# board_revB.net
KiCad netlist of a schematic drawn in EAGLE
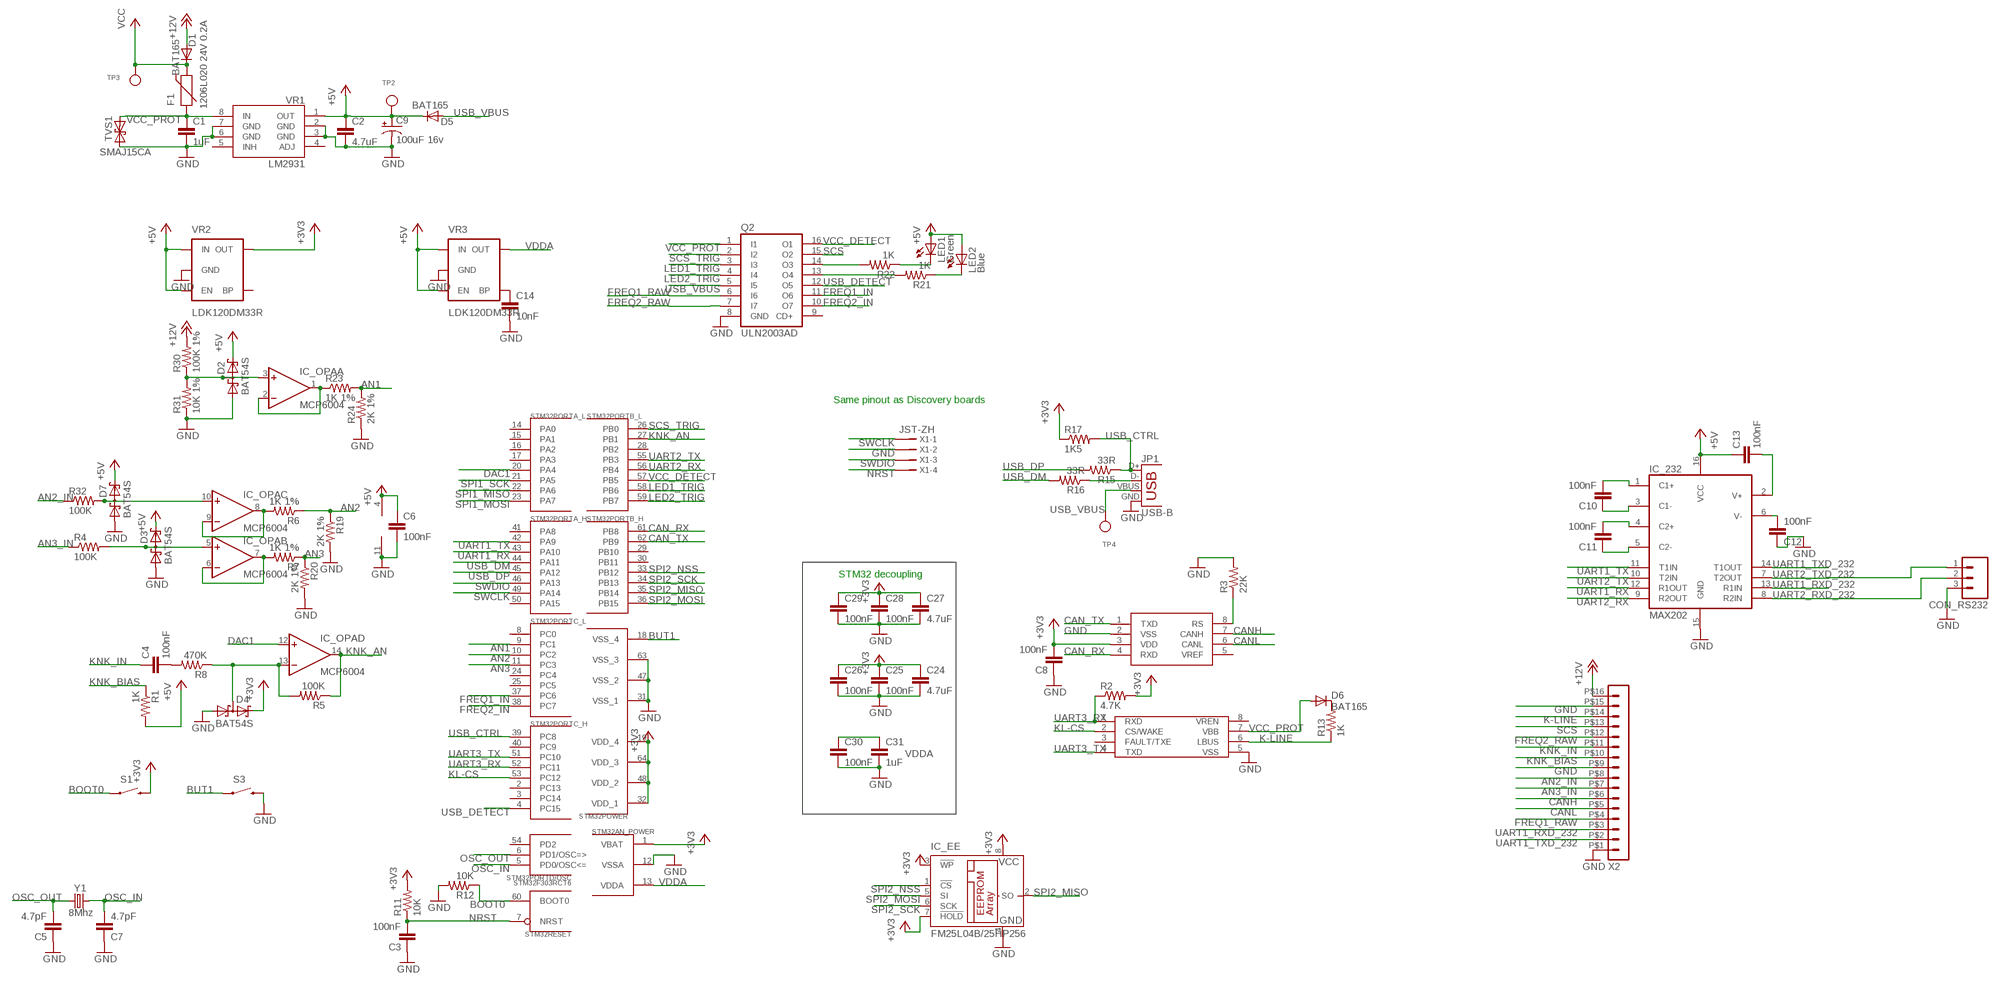
[diagram p0: schematic, sheet 1]

(export (version "E")
  (design (tool "Eeschema 10.0.6"))
  (components
    (comp (ref "C1")
      (value "1uF")
      (footprint "eagle-import:0603-CAP")
      (libsource (lib "eagle-import") (part "SparkFun-Passives_CAP0603-CAP"))
    )
    (comp (ref "C2")
      (value "4.7uF")
      (footprint "eagle-import:0603-CAP")
      (libsource (lib "eagle-import") (part "SparkFun-Passives_CAP0603-CAP"))
    )
    (comp (ref "C3")
      (value "100nF")
      (footprint "eagle-import:0603-CAP")
      (libsource (lib "eagle-import") (part "CAP0603-CAP"))
    )
    (comp (ref "C4")
      (value "100nF")
      (footprint "eagle-import:0603-CAP")
      (libsource (lib "eagle-import") (part "CAP0603-CAP"))
    )
    (comp (ref "C5")
      (value "4.7pF")
      (footprint "eagle-import:0603-CAP")
      (libsource (lib "eagle-import") (part "CAP0603-CAP"))
    )
    (comp (ref "C6")
      (value "100nF")
      (footprint "eagle-import:0603-CAP")
      (libsource (lib "eagle-import") (part "CAP0603-CAP"))
    )
    (comp (ref "C7")
      (value "4.7pF")
      (footprint "eagle-import:0603-CAP")
      (libsource (lib "eagle-import") (part "CAP0603-CAP"))
    )
    (comp (ref "C8")
      (value "100nF")
      (footprint "eagle-import:0603-CAP")
      (libsource (lib "eagle-import") (part "CAP0603-CAP"))
    )
    (comp (ref "C9")
      (value "100uF 16v")
      (footprint "eagle-import:CPOL-RADIAL-10UF-25V")
      (libsource (lib "eagle-import") (part "CAP_POLPTH2"))
    )
    (comp (ref "C10")
      (value "100nF")
      (footprint "eagle-import:0603-CAP")
      (libsource (lib "eagle-import") (part "CAP0603-CAP"))
    )
    (comp (ref "C11")
      (value "100nF")
      (footprint "eagle-import:0603-CAP")
      (libsource (lib "eagle-import") (part "CAP0603-CAP"))
    )
    (comp (ref "C12")
      (value "100nF")
      (footprint "eagle-import:0603-CAP")
      (libsource (lib "eagle-import") (part "CAP0603-CAP"))
    )
    (comp (ref "C13")
      (value "100nF")
      (footprint "eagle-import:0603-CAP")
      (libsource (lib "eagle-import") (part "CAP0603-CAP"))
    )
    (comp (ref "C14")
      (value "10nF")
      (footprint "eagle-import:0603-CAP")
      (libsource (lib "eagle-import") (part "CAP0603-CAP"))
    )
    (comp (ref "C24")
      (value "4.7uF")
      (footprint "eagle-import:0603-CAP")
      (libsource (lib "eagle-import") (part "SparkFun-Passives_CAP0603-CAP"))
    )
    (comp (ref "C25")
      (value "100nF")
      (footprint "eagle-import:0603-CAP")
      (libsource (lib "eagle-import") (part "CAP0603-CAP"))
    )
    (comp (ref "C26")
      (value "100nF")
      (footprint "eagle-import:0603-CAP")
      (libsource (lib "eagle-import") (part "CAP0603-CAP"))
    )
    (comp (ref "C27")
      (value "4.7uF")
      (footprint "eagle-import:0603-CAP")
      (libsource (lib "eagle-import") (part "SparkFun-Passives_CAP0603-CAP"))
    )
    (comp (ref "C28")
      (value "100nF")
      (footprint "eagle-import:0603-CAP")
      (libsource (lib "eagle-import") (part "CAP0603-CAP"))
    )
    (comp (ref "C29")
      (value "100nF")
      (footprint "eagle-import:0603-CAP")
      (libsource (lib "eagle-import") (part "CAP0603-CAP"))
    )
    (comp (ref "C30")
      (value "100nF")
      (footprint "eagle-import:0603-CAP")
      (libsource (lib "eagle-import") (part "CAP0603-CAP"))
    )
    (comp (ref "C31")
      (value "1uF")
      (footprint "eagle-import:0603-CAP")
      (libsource (lib "eagle-import") (part "CAP0603-CAP"))
    )
    (comp (ref "CON_RS232")
      (value "M03LOCK")
      (footprint "eagle-import:1X03_LOCK")
      (libsource (lib "eagle-import") (part "M03LOCK"))
    )
    (comp (ref "D1")
      (value "BAT165")
      (footprint "eagle-import:SOD-323")
      (libsource (lib "eagle-import") (part "DIODESOD"))
    )
    (comp (ref "D2")
      (value "BAT54S")
      (footprint "eagle-import:SOT23")
      (libsource (lib "eagle-import") (part "BAT54S"))
    )
    (comp (ref "D3")
      (value "BAT54S")
      (footprint "eagle-import:SOT23")
      (libsource (lib "eagle-import") (part "BAT54S"))
    )
    (comp (ref "D4")
      (value "BAT54S")
      (footprint "eagle-import:SOT23")
      (libsource (lib "eagle-import") (part "BAT54S"))
    )
    (comp (ref "D5")
      (value "BAT165")
      (footprint "eagle-import:SOD-323")
      (libsource (lib "eagle-import") (part "DIODESOD"))
    )
    (comp (ref "D6")
      (value "BAT165")
      (footprint "eagle-import:SOD-323")
      (libsource (lib "eagle-import") (part "DIODESOD"))
    )
    (comp (ref "D7")
      (value "BAT54S")
      (footprint "eagle-import:SOT23")
      (libsource (lib "eagle-import") (part "BAT54S"))
    )
    (comp (ref "F1")
      (value "1206L020 24V 0.2A")
      (footprint "eagle-import:PTC-1206")
      (libsource (lib "eagle-import") (part "PTCSMD"))
    )
    (comp (ref "IC_232")
      (value "MAX202")
      (footprint "eagle-import:TSSOP16")
      (libsource (lib "eagle-import") (part "MAX232TSSOP"))
    )
    (comp (ref "IC_CAN")
      (value "MAX3051")
      (footprint "eagle-import:SO08")
      (libsource (lib "eagle-import") (part "MCP2551"))
    )
    (comp (ref "IC_EE")
      (value "FM25L04B/25HP256")
      (footprint "eagle-import:SO-08")
      (fields (field (name "MF") "MICROCHIP") (field (name "MPN") "25LC080/SN"))
      (libsource (lib "eagle-import") (part "25SNLC080"))
    )
    (comp (ref "IC_KLINE")
      (value "TJA1027")
      (footprint "eagle-import:SO08")
      (libsource (lib "eagle-import") (part "MCP2004"))
    )
    (comp (ref "IC_OPA")
      (value "MCP6004")
      (footprint "eagle-import:TSSOP14")
      (libsource (lib "eagle-import") (part "LMV324?MZ"))
    )
    (comp (ref "JP1")
      (value "USB-B")
      (footprint "eagle-import:USB-B-PTH")
      (libsource (lib "eagle-import") (part "USBPTH"))
    )
    (comp (ref "LED1")
      (value "Green")
      (footprint "eagle-import:LED3MM")
      (libsource (lib "eagle-import") (part "LED3MM"))
    )
    (comp (ref "LED2")
      (value "Blue")
      (footprint "eagle-import:LED3MM")
      (libsource (lib "eagle-import") (part "LED3MM"))
    )
    (comp (ref "Q2")
      (value "ULN2003AD")
      (footprint "eagle-import:SO16")
      (libsource (lib "eagle-import") (part "ULN2003AD"))
    )
    (comp (ref "R1")
      (value "1K")
      (footprint "eagle-import:0603-RES")
      (libsource (lib "eagle-import") (part "RESISTOR0603-RES"))
    )
    (comp (ref "R2")
      (value "4.7K")
      (footprint "eagle-import:0603-RES")
      (libsource (lib "eagle-import") (part "RESISTOR0603-RES"))
    )
    (comp (ref "R3")
      (value "22K")
      (footprint "eagle-import:0603-RES")
      (libsource (lib "eagle-import") (part "RESISTOR0603-RES"))
    )
    (comp (ref "R4")
      (value "100K")
      (footprint "eagle-import:0603-RES")
      (libsource (lib "eagle-import") (part "RESISTOR0603-RES"))
    )
    (comp (ref "R5")
      (value "100K")
      (footprint "eagle-import:0603-RES")
      (libsource (lib "eagle-import") (part "RESISTOR0603-RES"))
    )
    (comp (ref "R6")
      (value "1K 1%")
      (footprint "eagle-import:0603-RES")
      (libsource (lib "eagle-import") (part "RESISTOR0603-RES"))
    )
    (comp (ref "R7")
      (value "1K 1%")
      (footprint "eagle-import:0603-RES")
      (libsource (lib "eagle-import") (part "RESISTOR0603-RES"))
    )
    (comp (ref "R8")
      (value "470K")
      (footprint "eagle-import:0603-RES")
      (libsource (lib "eagle-import") (part "RESISTOR0603-RES"))
    )
    (comp (ref "R11")
      (value "10K")
      (footprint "eagle-import:0603-RES")
      (libsource (lib "eagle-import") (part "RESISTOR0603-RES"))
    )
    (comp (ref "R12")
      (value "10K")
      (footprint "eagle-import:0603-RES")
      (libsource (lib "eagle-import") (part "RESISTOR0603-RES"))
    )
    (comp (ref "R13")
      (value "1K")
      (footprint "eagle-import:0603-RES")
      (libsource (lib "eagle-import") (part "RESISTOR0603-RES"))
    )
    (comp (ref "R15")
      (value "33R")
      (footprint "eagle-import:0603-RES")
      (libsource (lib "eagle-import") (part "RESISTOR0603-RES"))
    )
    (comp (ref "R16")
      (value "33R")
      (footprint "eagle-import:0603-RES")
      (libsource (lib "eagle-import") (part "RESISTOR0603-RES"))
    )
    (comp (ref "R17")
      (value "1K5")
      (footprint "eagle-import:0603-RES")
      (libsource (lib "eagle-import") (part "RESISTOR0603-RES"))
    )
    (comp (ref "R19")
      (value "2K 1%")
      (footprint "eagle-import:0603-RES")
      (libsource (lib "eagle-import") (part "RESISTOR0603-RES"))
    )
    (comp (ref "R20")
      (value "2K 1%")
      (footprint "eagle-import:0603-RES")
      (libsource (lib "eagle-import") (part "RESISTOR0603-RES"))
    )
    (comp (ref "R21")
      (value "1K")
      (footprint "eagle-import:0603-RES")
      (libsource (lib "eagle-import") (part "RESISTOR0603-RES"))
    )
    (comp (ref "R22")
      (value "1K")
      (footprint "eagle-import:0603-RES")
      (libsource (lib "eagle-import") (part "RESISTOR0603-RES"))
    )
    (comp (ref "R23")
      (value "1K 1%")
      (footprint "eagle-import:0603-RES")
      (libsource (lib "eagle-import") (part "RESISTOR0603-RES"))
    )
    (comp (ref "R24")
      (value "2K 1%")
      (footprint "eagle-import:0603-RES")
      (libsource (lib "eagle-import") (part "RESISTOR0603-RES"))
    )
    (comp (ref "R30")
      (value "100K 1%")
      (footprint "eagle-import:0603-RES")
      (libsource (lib "eagle-import") (part "RESISTOR0603-RES"))
    )
    (comp (ref "R31")
      (value "10K 1%")
      (footprint "eagle-import:0603-RES")
      (libsource (lib "eagle-import") (part "RESISTOR0603-RES"))
    )
    (comp (ref "R32")
      (value "100K")
      (footprint "eagle-import:0603-RES")
      (libsource (lib "eagle-import") (part "RESISTOR0603-RES"))
    )
    (comp (ref "S1")
      (value "SWITCH-MOMENTARY-2SMD-4")
      (footprint "eagle-import:TACTILE_SWITCH_TALL")
      (libsource (lib "eagle-import") (part "SWITCH-MOMENTARY-2SMD-4"))
    )
    (comp (ref "S3")
      (value "SWITCH-MOMENTARY-2SIDE_EZ")
      (footprint "eagle-import:TACTILE-PTH-SIDEEZ")
      (libsource (lib "eagle-import") (part "SWITCH-MOMENTARY-2SIDE_EZ"))
    )
    (comp (ref "STM32")
      (value "STM32F303RCT6")
      (footprint "eagle-import:TQFP64")
      (libsource (lib "eagle-import") (part "STM32F10XRXT6"))
    )
    (comp (ref "TP2")
      (value "TESTPOINTROUND1MM")
      (footprint "eagle-import:TESTPOINT_ROUND_1MM")
      (libsource (lib "eagle-import") (part "TESTPOINTROUND1MM"))
    )
    (comp (ref "TP3")
      (value "TESTPOINTROUND1MM")
      (footprint "eagle-import:TESTPOINT_ROUND_1MM")
      (libsource (lib "eagle-import") (part "TESTPOINTROUND1MM"))
    )
    (comp (ref "TP4")
      (value "TESTPOINTROUND1MM")
      (footprint "eagle-import:TESTPOINT_ROUND_1MM")
      (libsource (lib "eagle-import") (part "TESTPOINTROUND1MM"))
    )
    (comp (ref "TVS1")
      (value "SMAJ15CA")
      (footprint "eagle-import:SMA-DIODE")
      (libsource (lib "eagle-import") (part "TVS"))
    )
    (comp (ref "VR1")
      (value "LM2931")
      (footprint "eagle-import:SO08")
      (libsource (lib "eagle-import") (part "LM2931"))
    )
    (comp (ref "VR2")
      (value "LDK120DM33R")
      (footprint "eagle-import:SOT23-5")
      (libsource (lib "eagle-import") (part "V_REG_LDOSMD"))
    )
    (comp (ref "VR3")
      (value "LDK120DM33R")
      (footprint "eagle-import:SOT23-5")
      (libsource (lib "eagle-import") (part "V_REG_LDOSMD"))
    )
    (comp (ref "X1")
      (value "JST-ZH")
      (footprint "eagle-import:S4B-ZR")
      (fields (field (name "MF") "FARNELL") (field (name "MPN") "S4B-ZR(LF)(SN)"))
      (libsource (lib "eagle-import") (part "?4B-ZRS"))
    )
    (comp (ref "X2")
      (value "HEADER_POS16_43045-1600")
      (footprint "eagle-import:43045-1600")
      (libsource (lib "eagle-import") (part "HEADER_POS16_?43045-1600"))
    )
    (comp (ref "Y1")
      (value "8Mhz")
      (footprint "eagle-import:HC49US")
      (libsource (lib "eagle-import") (part "CRYSTALHC49US"))
    )
  )
  (nets
    (net (code "1") (name "+3V3") (class "Default")
      (node (ref "C24") (pin "1") (pinfunction "1_1") (pintype "passive"))
      (node (ref "C25") (pin "1") (pinfunction "1_1") (pintype "passive"))
      (node (ref "C26") (pin "1") (pinfunction "1_1") (pintype "passive"))
      (node (ref "C27") (pin "1") (pinfunction "1_1") (pintype "passive"))
      (node (ref "C28") (pin "1") (pinfunction "1_1") (pintype "passive"))
      (node (ref "C29") (pin "1") (pinfunction "1_1") (pintype "passive"))
      (node (ref "C8") (pin "2") (pinfunction "2_2") (pintype "passive"))
      (node (ref "D4") (pin "2") (pinfunction "C2_2") (pintype "passive"))
      (node (ref "IC_CAN") (pin "3") (pinfunction "VDD_3") (pintype "bidirectional"))
      (node (ref "IC_EE") (pin "3") (pinfunction "~{WP}_3") (pintype "input"))
      (node (ref "IC_EE") (pin "7") (pinfunction "~{HOLD}_7") (pintype "input"))
      (node (ref "IC_EE") (pin "8") (pinfunction "VCC_8") (pintype "power_in"))
      (node (ref "R11") (pin "2") (pinfunction "2_2") (pintype "passive"))
      (node (ref "R17") (pin "1") (pinfunction "1_1") (pintype "passive"))
      (node (ref "R2") (pin "2") (pinfunction "2_2") (pintype "passive"))
      (node (ref "S1") (pin "B2") (pinfunction "2_B2") (pintype "passive"))
      (node (ref "STM32") (pin "1") (pinfunction "VBAT_1") (pintype "power_in"))
      (node (ref "STM32") (pin "19") (pinfunction "VDD_4_19") (pintype "power_in"))
      (node (ref "STM32") (pin "32") (pinfunction "VDD_1_32") (pintype "power_in"))
      (node (ref "STM32") (pin "48") (pinfunction "VDD_2_48") (pintype "power_in"))
      (node (ref "STM32") (pin "64") (pinfunction "VDD_3_64") (pintype "power_in"))
      (node (ref "VR2") (pin "5") (pinfunction "OUT_5") (pintype "passive"))
    )
    (net (code "2") (name "+5V") (class "Default")
      (node (ref "C13") (pin "1") (pinfunction "1_1") (pintype "passive"))
      (node (ref "C2") (pin "1") (pinfunction "1_1") (pintype "passive"))
      (node (ref "C6") (pin "1") (pinfunction "1_1") (pintype "passive"))
      (node (ref "C9") (pin "1") (pinfunction "+_1") (pintype "passive"))
      (node (ref "D2") (pin "2") (pinfunction "C2_2") (pintype "passive"))
      (node (ref "D3") (pin "2") (pinfunction "C2_2") (pintype "passive"))
      (node (ref "D5") (pin "1") (pinfunction "C_1") (pintype "passive"))
      (node (ref "D7") (pin "2") (pinfunction "C2_2") (pintype "passive"))
      (node (ref "IC_232") (pin "16") (pinfunction "VCC_16") (pintype "bidirectional"))
      (node (ref "IC_OPA") (pin "4") (pinfunction "V+_4") (pintype "power_in"))
      (node (ref "LED1") (pin "A") (pinfunction "A_A") (pintype "passive"))
      (node (ref "LED2") (pin "A") (pinfunction "A_A") (pintype "passive"))
      (node (ref "R1") (pin "2") (pinfunction "2_2") (pintype "passive"))
      (node (ref "TP2") (pin "P$1") (pinfunction "P$1_P$1") (pintype "bidirectional"))
      (node (ref "VR1") (pin "1") (pinfunction "OUT_1") (pintype "bidirectional"))
      (node (ref "VR2") (pin "1") (pinfunction "IN_1") (pintype "input"))
      (node (ref "VR2") (pin "3") (pinfunction "EN_3") (pintype "input"))
      (node (ref "VR3") (pin "1") (pinfunction "IN_1") (pintype "input"))
      (node (ref "VR3") (pin "3") (pinfunction "EN_3") (pintype "input"))
    )
    (net (code "3") (name "+12V") (class "Default")
      (node (ref "D1") (pin "2") (pinfunction "A_2") (pintype "passive"))
      (node (ref "R30") (pin "2") (pinfunction "2_2") (pintype "passive"))
      (node (ref "X2") (pin "P$16") (pinfunction "16_P$16") (pintype "passive"))
    )
    (net (code "4") (name "/AN1") (class "Default")
      (node (ref "R23") (pin "2") (pinfunction "2_2") (pintype "passive"))
      (node (ref "R24") (pin "2") (pinfunction "2_2") (pintype "passive"))
      (node (ref "STM32") (pin "9") (pinfunction "PC1_9") (pintype "bidirectional"))
    )
    (net (code "5") (name "/AN2") (class "Default")
      (node (ref "R19") (pin "1") (pinfunction "1_1") (pintype "passive"))
      (node (ref "R6") (pin "1") (pinfunction "1_1") (pintype "passive"))
      (node (ref "STM32") (pin "10") (pinfunction "PC2_10") (pintype "bidirectional"))
    )
    (net (code "6") (name "/AN2_IN") (class "Default")
      (node (ref "R32") (pin "1") (pinfunction "1_1") (pintype "passive"))
      (node (ref "X2") (pin "P$8") (pinfunction "8_P$8") (pintype "passive"))
    )
    (net (code "7") (name "/AN3") (class "Default")
      (node (ref "R20") (pin "1") (pinfunction "1_1") (pintype "passive"))
      (node (ref "R7") (pin "1") (pinfunction "1_1") (pintype "passive"))
      (node (ref "STM32") (pin "11") (pinfunction "PC3_11") (pintype "bidirectional"))
    )
    (net (code "8") (name "/AN3_IN") (class "Default")
      (node (ref "R4") (pin "1") (pinfunction "1_1") (pintype "passive"))
      (node (ref "X2") (pin "P$7") (pinfunction "7_P$7") (pintype "passive"))
    )
    (net (code "9") (name "/BOOT0") (class "Default")
      (node (ref "R12") (pin "1") (pinfunction "1_1") (pintype "passive"))
      (node (ref "S1") (pin "A2") (pinfunction "1_A2") (pintype "passive"))
      (node (ref "STM32") (pin "60") (pinfunction "BOOT0_60") (pintype "input"))
    )
    (net (code "10") (name "/BUT1") (class "Default")
      (node (ref "S3") (pin "1") (pinfunction "1_1") (pintype "passive"))
      (node (ref "STM32") (pin "18") (pinfunction "VSS_4_18") (pintype "power_in"))
    )
    (net (code "11") (name "/CANH") (class "Default")
      (node (ref "IC_CAN") (pin "7") (pinfunction "CANH_7") (pintype "bidirectional"))
      (node (ref "X2") (pin "P$6") (pinfunction "6_P$6") (pintype "passive"))
    )
    (net (code "12") (name "/CANL") (class "Default")
      (node (ref "IC_CAN") (pin "6") (pinfunction "CANL_6") (pintype "bidirectional"))
      (node (ref "X2") (pin "P$5") (pinfunction "5_P$5") (pintype "passive"))
    )
    (net (code "13") (name "/CAN_RX") (class "Default")
      (node (ref "IC_CAN") (pin "4") (pinfunction "RXD_4") (pintype "bidirectional"))
      (node (ref "STM32") (pin "61") (pinfunction "PB8_61") (pintype "bidirectional"))
    )
    (net (code "14") (name "/CAN_TX") (class "Default")
      (node (ref "IC_CAN") (pin "1") (pinfunction "TXD_1") (pintype "bidirectional"))
      (node (ref "STM32") (pin "62") (pinfunction "PB9_62") (pintype "bidirectional"))
    )
    (net (code "15") (name "/DAC1") (class "Default")
      (node (ref "IC_OPA") (pin "12") (pinfunction "+IN_12") (pintype "input"))
      (node (ref "STM32") (pin "20") (pinfunction "PA4_20") (pintype "bidirectional"))
    )
    (net (code "16") (name "/FREQ1_IN") (class "Default")
      (node (ref "Q2") (pin "11") (pinfunction "O6_11") (pintype "open_collector"))
      (node (ref "STM32") (pin "37") (pinfunction "PC6_37") (pintype "bidirectional"))
    )
    (net (code "17") (name "/FREQ1_RAW") (class "Default")
      (node (ref "Q2") (pin "6") (pinfunction "I6_6") (pintype "input"))
      (node (ref "X2") (pin "P$4") (pinfunction "4_P$4") (pintype "passive"))
    )
    (net (code "18") (name "/FREQ2_IN") (class "Default")
      (node (ref "Q2") (pin "10") (pinfunction "O7_10") (pintype "open_collector"))
      (node (ref "STM32") (pin "38") (pinfunction "PC7_38") (pintype "bidirectional"))
    )
    (net (code "19") (name "/FREQ2_RAW") (class "Default")
      (node (ref "Q2") (pin "7") (pinfunction "I7_7") (pintype "input"))
      (node (ref "X2") (pin "P$12") (pinfunction "12_P$12") (pintype "passive"))
    )
    (net (code "20") (name "/K-LINE") (class "Default")
      (node (ref "IC_KLINE") (pin "6") (pinfunction "LBUS_6") (pintype "bidirectional"))
      (node (ref "R13") (pin "1") (pinfunction "1_1") (pintype "passive"))
      (node (ref "X2") (pin "P$14") (pinfunction "14_P$14") (pintype "passive"))
    )
    (net (code "21") (name "/KL-CS") (class "Default")
      (node (ref "IC_KLINE") (pin "2") (pinfunction "CS/WAKE_2") (pintype "bidirectional"))
      (node (ref "STM32") (pin "53") (pinfunction "PC12_53") (pintype "bidirectional"))
    )
    (net (code "22") (name "/KNK_AN") (class "Default")
      (node (ref "IC_OPA") (pin "14") (pinfunction "OUT_14") (pintype "output"))
      (node (ref "R5") (pin "1") (pinfunction "1_1") (pintype "passive"))
      (node (ref "STM32") (pin "27") (pinfunction "PB1_27") (pintype "bidirectional"))
    )
    (net (code "23") (name "/KNK_BIAS") (class "Default")
      (node (ref "R1") (pin "1") (pinfunction "1_1") (pintype "passive"))
      (node (ref "X2") (pin "P$10") (pinfunction "10_P$10") (pintype "passive"))
    )
    (net (code "24") (name "/KNK_IN") (class "Default")
      (node (ref "C4") (pin "1") (pinfunction "1_1") (pintype "passive"))
      (node (ref "X2") (pin "P$11") (pinfunction "11_P$11") (pintype "passive"))
    )
    (net (code "25") (name "/LED1_TRIG") (class "Default")
      (node (ref "Q2") (pin "3") (pinfunction "I3_3") (pintype "input"))
      (node (ref "STM32") (pin "58") (pinfunction "PB6_58") (pintype "bidirectional"))
    )
    (net (code "26") (name "/LED2_TRIG") (class "Default")
      (node (ref "Q2") (pin "4") (pinfunction "I4_4") (pintype "input"))
      (node (ref "STM32") (pin "59") (pinfunction "PB7_59") (pintype "bidirectional"))
    )
    (net (code "27") (name "/NRST") (class "Default")
      (node (ref "C3") (pin "2") (pinfunction "2_2") (pintype "passive"))
      (node (ref "R11") (pin "1") (pinfunction "1_1") (pintype "passive"))
      (node (ref "STM32") (pin "7") (pinfunction "NRST_7") (pintype "input"))
      (node (ref "X1") (pin "4") (pinfunction "1_4") (pintype "passive"))
    )
    (net (code "28") (name "/OSC_IN") (class "Default")
      (node (ref "C7") (pin "2") (pinfunction "2_2") (pintype "passive"))
      (node (ref "STM32") (pin "5") (pinfunction "PD0/OSC<=_5") (pintype "bidirectional"))
      (node (ref "Y1") (pin "2") (pinfunction "2_2") (pintype "passive"))
    )
    (net (code "29") (name "/OSC_OUT") (class "Default")
      (node (ref "C5") (pin "2") (pinfunction "2_2") (pintype "passive"))
      (node (ref "STM32") (pin "6") (pinfunction "PD1/OSC=>_6") (pintype "bidirectional"))
      (node (ref "Y1") (pin "1") (pinfunction "1_1") (pintype "passive"))
    )
    (net (code "30") (name "/SCS") (class "Default")
      (node (ref "Q2") (pin "15") (pinfunction "O2_15") (pintype "open_collector"))
      (node (ref "X2") (pin "P$13") (pinfunction "13_P$13") (pintype "passive"))
    )
    (net (code "31") (name "/SCS_TRIG") (class "Default")
      (node (ref "Q2") (pin "2") (pinfunction "I2_2") (pintype "input"))
      (node (ref "STM32") (pin "26") (pinfunction "PB0_26") (pintype "bidirectional"))
    )
    (net (code "32") (name "/SPI1_MISO") (class "Default")
      (node (ref "STM32") (pin "22") (pinfunction "PA6_22") (pintype "bidirectional"))
    )
    (net (code "33") (name "/SPI1_MOSI") (class "Default")
      (node (ref "STM32") (pin "23") (pinfunction "PA7_23") (pintype "bidirectional"))
    )
    (net (code "34") (name "/SPI1_SCK") (class "Default")
      (node (ref "STM32") (pin "21") (pinfunction "PA5_21") (pintype "bidirectional"))
    )
    (net (code "35") (name "/SPI2_MISO") (class "Default")
      (node (ref "IC_EE") (pin "2") (pinfunction "SO_2") (pintype "bidirectional"))
      (node (ref "STM32") (pin "35") (pinfunction "PB14_35") (pintype "bidirectional"))
    )
    (net (code "36") (name "/SPI2_MOSI") (class "Default")
      (node (ref "IC_EE") (pin "5") (pinfunction "SI_5") (pintype "input"))
      (node (ref "STM32") (pin "36") (pinfunction "PB15_36") (pintype "bidirectional"))
    )
    (net (code "37") (name "/SPI2_NSS") (class "Default")
      (node (ref "IC_EE") (pin "1") (pinfunction "~{CS}_1") (pintype "input"))
      (node (ref "STM32") (pin "33") (pinfunction "PB12_33") (pintype "bidirectional"))
    )
    (net (code "38") (name "/SPI2_SCK") (class "Default")
      (node (ref "IC_EE") (pin "6") (pinfunction "SCK_6") (pintype "input"))
      (node (ref "STM32") (pin "34") (pinfunction "PB13_34") (pintype "bidirectional"))
    )
    (net (code "39") (name "/SWCLK") (class "Default")
      (node (ref "STM32") (pin "49") (pinfunction "PA14_49") (pintype "bidirectional"))
      (node (ref "X1") (pin "1") (pinfunction "1_1") (pintype "passive"))
    )
    (net (code "40") (name "/SWDIO") (class "Default")
      (node (ref "STM32") (pin "46") (pinfunction "PA13_46") (pintype "bidirectional"))
      (node (ref "X1") (pin "3") (pinfunction "1_3") (pintype "passive"))
    )
    (net (code "41") (name "/UART1_RX") (class "Default")
      (node (ref "IC_232") (pin "12") (pinfunction "R1OUT_12") (pintype "output"))
      (node (ref "STM32") (pin "43") (pinfunction "PA10_43") (pintype "bidirectional"))
    )
    (net (code "42") (name "/UART1_RXD_232") (class "Default")
      (node (ref "IC_232") (pin "13") (pinfunction "R1IN_13") (pintype "input"))
      (node (ref "X2") (pin "P$3") (pinfunction "3_P$3") (pintype "passive"))
    )
    (net (code "43") (name "/UART1_TX") (class "Default")
      (node (ref "IC_232") (pin "11") (pinfunction "T1IN_11") (pintype "input"))
      (node (ref "STM32") (pin "42") (pinfunction "PA9_42") (pintype "bidirectional"))
    )
    (net (code "44") (name "/UART1_TXD_232") (class "Default")
      (node (ref "IC_232") (pin "14") (pinfunction "T1OUT_14") (pintype "output"))
      (node (ref "X2") (pin "P$2") (pinfunction "2_P$2") (pintype "passive"))
    )
    (net (code "45") (name "/UART2_RX") (class "Default")
      (node (ref "IC_232") (pin "9") (pinfunction "R2OUT_9") (pintype "output"))
      (node (ref "STM32") (pin "56") (pinfunction "PB4_56") (pintype "bidirectional"))
    )
    (net (code "46") (name "/UART2_RXD_232") (class "Default")
      (node (ref "CON_RS232") (pin "2") (pinfunction "2_2") (pintype "passive"))
      (node (ref "IC_232") (pin "8") (pinfunction "R2IN_8") (pintype "input"))
    )
    (net (code "47") (name "/UART2_TX") (class "Default")
      (node (ref "IC_232") (pin "10") (pinfunction "T2IN_10") (pintype "input"))
      (node (ref "STM32") (pin "55") (pinfunction "PB3_55") (pintype "bidirectional"))
    )
    (net (code "48") (name "/UART2_TXD_232") (class "Default")
      (node (ref "CON_RS232") (pin "1") (pinfunction "1_1") (pintype "passive"))
      (node (ref "IC_232") (pin "7") (pinfunction "T2OUT_7") (pintype "output"))
    )
    (net (code "49") (name "/UART3_RX") (class "Default")
      (node (ref "IC_KLINE") (pin "1") (pinfunction "RXD_1") (pintype "bidirectional"))
      (node (ref "R2") (pin "1") (pinfunction "1_1") (pintype "passive"))
      (node (ref "STM32") (pin "52") (pinfunction "PC11_52") (pintype "bidirectional"))
    )
    (net (code "50") (name "/UART3_TX") (class "Default")
      (node (ref "IC_KLINE") (pin "4") (pinfunction "TXD_4") (pintype "bidirectional"))
      (node (ref "STM32") (pin "51") (pinfunction "PC10_51") (pintype "bidirectional"))
    )
    (net (code "51") (name "/USB_CTRL") (class "Default")
      (node (ref "JP1") (pin "D+") (pinfunction "D+_D+") (pintype "bidirectional"))
      (node (ref "R15") (pin "1") (pinfunction "1_1") (pintype "passive"))
      (node (ref "R17") (pin "2") (pinfunction "2_2") (pintype "passive"))
      (node (ref "STM32") (pin "39") (pinfunction "PC8_39") (pintype "bidirectional"))
    )
    (net (code "52") (name "/USB_DETECT") (class "Default")
      (node (ref "Q2") (pin "12") (pinfunction "O5_12") (pintype "open_collector"))
      (node (ref "STM32") (pin "4") (pinfunction "PC15_4") (pintype "bidirectional"))
    )
    (net (code "53") (name "/USB_DM") (class "Default")
      (node (ref "R16") (pin "2") (pinfunction "2_2") (pintype "passive"))
      (node (ref "STM32") (pin "44") (pinfunction "PA11_44") (pintype "bidirectional"))
    )
    (net (code "54") (name "/USB_DP") (class "Default")
      (node (ref "R15") (pin "2") (pinfunction "2_2") (pintype "passive"))
      (node (ref "STM32") (pin "45") (pinfunction "PA12_45") (pintype "bidirectional"))
    )
    (net (code "55") (name "/USB_VBUS") (class "Default")
      (node (ref "D5") (pin "2") (pinfunction "A_2") (pintype "passive"))
      (node (ref "JP1") (pin "VBUS") (pinfunction "VBUS_VBUS") (pintype "bidirectional"))
      (node (ref "Q2") (pin "5") (pinfunction "I5_5") (pintype "input"))
      (node (ref "TP4") (pin "P$1") (pinfunction "P$1_P$1") (pintype "bidirectional"))
    )
    (net (code "56") (name "/VCC_DETECT") (class "Default")
      (node (ref "Q2") (pin "16") (pinfunction "O1_16") (pintype "open_collector"))
      (node (ref "STM32") (pin "57") (pinfunction "PB5_57") (pintype "bidirectional"))
    )
    (net (code "57") (name "/VCC_PROT") (class "Default")
      (node (ref "C1") (pin "1") (pinfunction "1_1") (pintype "passive"))
      (node (ref "D6") (pin "2") (pinfunction "A_2") (pintype "passive"))
      (node (ref "F1") (pin "1") (pinfunction "1_1") (pintype "bidirectional"))
      (node (ref "IC_KLINE") (pin "7") (pinfunction "VBB_7") (pintype "bidirectional"))
      (node (ref "Q2") (pin "1") (pinfunction "I1_1") (pintype "input"))
      (node (ref "TVS1") (pin "C") (pinfunction "2_C") (pintype "passive"))
      (node (ref "VR1") (pin "8") (pinfunction "IN_8") (pintype "bidirectional"))
    )
    (net (code "58") (name "/VDDA") (class "Default")
      (node (ref "C30") (pin "1") (pinfunction "1_1") (pintype "passive"))
      (node (ref "C31") (pin "1") (pinfunction "1_1") (pintype "passive"))
      (node (ref "STM32") (pin "13") (pinfunction "VDDA_13") (pintype "power_in"))
      (node (ref "VR3") (pin "5") (pinfunction "OUT_5") (pintype "passive"))
    )
    (net (code "59") (name "GND") (class "Default")
      (node (ref "C1") (pin "2") (pinfunction "2_2") (pintype "passive"))
      (node (ref "C12") (pin "1") (pinfunction "1_1") (pintype "passive"))
      (node (ref "C14") (pin "2") (pinfunction "2_2") (pintype "passive"))
      (node (ref "C2") (pin "2") (pinfunction "2_2") (pintype "passive"))
      (node (ref "C24") (pin "2") (pinfunction "2_2") (pintype "passive"))
      (node (ref "C25") (pin "2") (pinfunction "2_2") (pintype "passive"))
      (node (ref "C26") (pin "2") (pinfunction "2_2") (pintype "passive"))
      (node (ref "C27") (pin "2") (pinfunction "2_2") (pintype "passive"))
      (node (ref "C28") (pin "2") (pinfunction "2_2") (pintype "passive"))
      (node (ref "C29") (pin "2") (pinfunction "2_2") (pintype "passive"))
      (node (ref "C3") (pin "1") (pinfunction "1_1") (pintype "passive"))
      (node (ref "C30") (pin "2") (pinfunction "2_2") (pintype "passive"))
      (node (ref "C31") (pin "2") (pinfunction "2_2") (pintype "passive"))
      (node (ref "C5") (pin "1") (pinfunction "1_1") (pintype "passive"))
      (node (ref "C6") (pin "2") (pinfunction "2_2") (pintype "passive"))
      (node (ref "C7") (pin "1") (pinfunction "1_1") (pintype "passive"))
      (node (ref "C8") (pin "1") (pinfunction "1_1") (pintype "passive"))
      (node (ref "C9") (pin "2") (pinfunction "-_2") (pintype "passive"))
      (node (ref "CON_RS232") (pin "3") (pinfunction "3_3") (pintype "passive"))
      (node (ref "D2") (pin "1") (pinfunction "A1_1") (pintype "passive"))
      (node (ref "D3") (pin "1") (pinfunction "A1_1") (pintype "passive"))
      (node (ref "D4") (pin "1") (pinfunction "A1_1") (pintype "passive"))
      (node (ref "D7") (pin "1") (pinfunction "A1_1") (pintype "passive"))
      (node (ref "IC_232") (pin "15") (pinfunction "GND_15") (pintype "bidirectional"))
      (node (ref "IC_CAN") (pin "2") (pinfunction "VSS_2") (pintype "bidirectional"))
      (node (ref "IC_EE") (pin "4") (pinfunction "GND_4") (pintype "power_in"))
      (node (ref "IC_KLINE") (pin "5") (pinfunction "VSS_5") (pintype "bidirectional"))
      (node (ref "IC_OPA") (pin "11") (pinfunction "V-_11") (pintype "power_in"))
      (node (ref "JP1") (pin "GND") (pinfunction "GND_GND") (pintype "bidirectional"))
      (node (ref "Q2") (pin "8") (pinfunction "GND_8") (pintype "power_in"))
      (node (ref "R12") (pin "2") (pinfunction "2_2") (pintype "passive"))
      (node (ref "R19") (pin "2") (pinfunction "2_2") (pintype "passive"))
      (node (ref "R20") (pin "2") (pinfunction "2_2") (pintype "passive"))
      (node (ref "R24") (pin "1") (pinfunction "1_1") (pintype "passive"))
      (node (ref "R3") (pin "2") (pinfunction "2_2") (pintype "passive"))
      (node (ref "R31") (pin "1") (pinfunction "1_1") (pintype "passive"))
      (node (ref "S3") (pin "2") (pinfunction "2_2") (pintype "passive"))
      (node (ref "STM32") (pin "12") (pinfunction "VSSA_12") (pintype "power_in"))
      (node (ref "STM32") (pin "31") (pinfunction "VSS_1_31") (pintype "power_in"))
      (node (ref "STM32") (pin "47") (pinfunction "VSS_2_47") (pintype "power_in"))
      (node (ref "STM32") (pin "63") (pinfunction "VSS_3_63") (pintype "power_in"))
      (node (ref "TVS1") (pin "A") (pinfunction "1_A") (pintype "passive"))
      (node (ref "VR1") (pin "2") (pinfunction "GND_2") (pintype "bidirectional"))
      (node (ref "VR1") (pin "3") (pinfunction "GND_3") (pintype "bidirectional"))
      (node (ref "VR1") (pin "6") (pinfunction "GND_6") (pintype "bidirectional"))
      (node (ref "VR1") (pin "7") (pinfunction "GND_7") (pintype "bidirectional"))
      (node (ref "VR2") (pin "2") (pinfunction "GND_2") (pintype "input"))
      (node (ref "VR3") (pin "2") (pinfunction "GND_2") (pintype "input"))
      (node (ref "X1") (pin "2") (pinfunction "1_2") (pintype "passive"))
      (node (ref "X2") (pin "P$1") (pinfunction "1_P$1") (pintype "passive"))
      (node (ref "X2") (pin "P$15") (pinfunction "15_P$15") (pintype "passive"))
      (node (ref "X2") (pin "P$9") (pinfunction "9_P$9") (pintype "passive"))
    )
    (net (code "60") (name "Net-(C4-Pad2)") (class "Default")
      (node (ref "C4") (pin "2") (pinfunction "2_2") (pintype "passive"))
      (node (ref "R8") (pin "2") (pinfunction "2_2") (pintype "passive"))
    )
    (net (code "61") (name "Net-(D2-C1A2)") (class "Default")
      (node (ref "D2") (pin "3") (pinfunction "C1A2_3") (pintype "passive"))
      (node (ref "IC_OPA") (pin "3") (pinfunction "+IN_3") (pintype "input"))
      (node (ref "R30") (pin "1") (pinfunction "1_1") (pintype "passive"))
      (node (ref "R31") (pin "2") (pinfunction "2_2") (pintype "passive"))
    )
    (net (code "62") (name "Net-(D3-C1A2)") (class "Default")
      (node (ref "D3") (pin "3") (pinfunction "C1A2_3") (pintype "passive"))
      (node (ref "IC_OPA") (pin "5") (pinfunction "+IN_5") (pintype "input"))
      (node (ref "R4") (pin "2") (pinfunction "2_2") (pintype "passive"))
    )
    (net (code "63") (name "Net-(D4-C1A2)") (class "Default")
      (node (ref "D4") (pin "3") (pinfunction "C1A2_3") (pintype "passive"))
      (node (ref "IC_OPA") (pin "13") (pinfunction "-IN_13") (pintype "input"))
      (node (ref "R5") (pin "2") (pinfunction "2_2") (pintype "passive"))
      (node (ref "R8") (pin "1") (pinfunction "1_1") (pintype "passive"))
    )
    (net (code "64") (name "Net-(D6-C)") (class "Default")
      (node (ref "D6") (pin "1") (pinfunction "C_1") (pintype "passive"))
      (node (ref "R13") (pin "2") (pinfunction "2_2") (pintype "passive"))
    )
    (net (code "65") (name "Net-(D7-C1A2)") (class "Default")
      (node (ref "D7") (pin "3") (pinfunction "C1A2_3") (pintype "passive"))
      (node (ref "IC_OPA") (pin "10") (pinfunction "+IN_10") (pintype "input"))
      (node (ref "R32") (pin "2") (pinfunction "2_2") (pintype "passive"))
    )
    (net (code "66") (name "Net-(IC_232-C1+)") (class "Default")
      (node (ref "C10") (pin "2") (pinfunction "2_2") (pintype "passive"))
      (node (ref "IC_232") (pin "1") (pinfunction "C1+_1") (pintype "bidirectional"))
    )
    (net (code "67") (name "Net-(IC_232-C1-)") (class "Default")
      (node (ref "C10") (pin "1") (pinfunction "1_1") (pintype "passive"))
      (node (ref "IC_232") (pin "3") (pinfunction "C1-_3") (pintype "bidirectional"))
    )
    (net (code "68") (name "Net-(IC_232-C2+)") (class "Default")
      (node (ref "C11") (pin "2") (pinfunction "2_2") (pintype "passive"))
      (node (ref "IC_232") (pin "4") (pinfunction "C2+_4") (pintype "bidirectional"))
    )
    (net (code "69") (name "Net-(IC_232-C2-)") (class "Default")
      (node (ref "C11") (pin "1") (pinfunction "1_1") (pintype "passive"))
      (node (ref "IC_232") (pin "5") (pinfunction "C2-_5") (pintype "bidirectional"))
    )
    (net (code "70") (name "Net-(IC_232-V+)") (class "Default")
      (node (ref "C13") (pin "2") (pinfunction "2_2") (pintype "passive"))
      (node (ref "IC_232") (pin "2") (pinfunction "V+_2") (pintype "bidirectional"))
    )
    (net (code "71") (name "Net-(IC_232-V-)") (class "Default")
      (node (ref "C12") (pin "2") (pinfunction "2_2") (pintype "passive"))
      (node (ref "IC_232") (pin "6") (pinfunction "V-_6") (pintype "bidirectional"))
    )
    (net (code "72") (name "Net-(IC_CAN-RS)") (class "Default")
      (node (ref "IC_CAN") (pin "8") (pinfunction "RS_8") (pintype "bidirectional"))
      (node (ref "R3") (pin "1") (pinfunction "1_1") (pintype "passive"))
    )
    (net (code "73") (name "Net-(IC_OPAA--IN)") (class "Default")
      (node (ref "IC_OPA") (pin "1") (pinfunction "OUT_1") (pintype "output"))
      (node (ref "IC_OPA") (pin "2") (pinfunction "-IN_2") (pintype "input"))
      (node (ref "R23") (pin "1") (pinfunction "1_1") (pintype "passive"))
    )
    (net (code "74") (name "Net-(IC_OPAB--IN)") (class "Default")
      (node (ref "IC_OPA") (pin "6") (pinfunction "-IN_6") (pintype "input"))
      (node (ref "IC_OPA") (pin "7") (pinfunction "OUT_7") (pintype "output"))
      (node (ref "R7") (pin "2") (pinfunction "2_2") (pintype "passive"))
    )
    (net (code "75") (name "Net-(IC_OPAC--IN)") (class "Default")
      (node (ref "IC_OPA") (pin "8") (pinfunction "OUT_8") (pintype "output"))
      (node (ref "IC_OPA") (pin "9") (pinfunction "-IN_9") (pintype "input"))
      (node (ref "R6") (pin "2") (pinfunction "2_2") (pintype "passive"))
    )
    (net (code "76") (name "Net-(JP1-PadD-)") (class "Default")
      (node (ref "JP1") (pin "D-") (pinfunction "D-_D-") (pintype "bidirectional"))
      (node (ref "R16") (pin "1") (pinfunction "1_1") (pintype "passive"))
    )
    (net (code "77") (name "Net-(LED1-C)") (class "Default")
      (node (ref "LED1") (pin "K") (pinfunction "C_K") (pintype "passive"))
      (node (ref "R22") (pin "1") (pinfunction "1_1") (pintype "passive"))
    )
    (net (code "78") (name "Net-(LED2-C)") (class "Default")
      (node (ref "LED2") (pin "K") (pinfunction "C_K") (pintype "passive"))
      (node (ref "R21") (pin "1") (pinfunction "1_1") (pintype "passive"))
    )
    (net (code "79") (name "Net-(Q2-O3)") (class "Default")
      (node (ref "Q2") (pin "14") (pinfunction "O3_14") (pintype "open_collector"))
      (node (ref "R22") (pin "2") (pinfunction "2_2") (pintype "passive"))
    )
    (net (code "80") (name "Net-(Q2-O4)") (class "Default")
      (node (ref "Q2") (pin "13") (pinfunction "O4_13") (pintype "open_collector"))
      (node (ref "R21") (pin "2") (pinfunction "2_2") (pintype "passive"))
    )
    (net (code "81") (name "Net-(VR3-BP)") (class "Default")
      (node (ref "C14") (pin "1") (pinfunction "1_1") (pintype "passive"))
      (node (ref "VR3") (pin "4") (pinfunction "BP_4") (pintype "input"))
    )
    (net (code "82") (name "VCC") (class "Default")
      (node (ref "D1") (pin "1") (pinfunction "C_1") (pintype "passive"))
      (node (ref "F1") (pin "2") (pinfunction "2_2") (pintype "bidirectional"))
      (node (ref "TP3") (pin "P$1") (pinfunction "P$1_P$1") (pintype "bidirectional"))
    )
    (net (code "83") (name "unconnected-(IC_CAN-VREF-Pad5)") (class "Default")
      (node (ref "IC_CAN") (pin "5") (pinfunction "VREF_5") (pintype "bidirectional"))
    )
    (net (code "84") (name "unconnected-(IC_KLINE-FAULT{slash}TXE-Pad3)") (class "Default")
      (node (ref "IC_KLINE") (pin "3") (pinfunction "FAULT/TXE_3") (pintype "bidirectional"))
    )
    (net (code "85") (name "unconnected-(IC_KLINE-VREN-Pad8)") (class "Default")
      (node (ref "IC_KLINE") (pin "8") (pinfunction "VREN_8") (pintype "bidirectional"))
    )
    (net (code "86") (name "unconnected-(Q2-CD+-Pad9)") (class "Default")
      (node (ref "Q2") (pin "9") (pinfunction "CD+_9") (pintype "passive"))
    )
    (net (code "87") (name "unconnected-(STM32B-PA8-Pad41)") (class "Default")
      (node (ref "STM32") (pin "41") (pinfunction "PA8_41") (pintype "bidirectional"))
    )
    (net (code "88") (name "unconnected-(STM32B-PA15-Pad50)") (class "Default")
      (node (ref "STM32") (pin "50") (pinfunction "PA15_50") (pintype "bidirectional"))
    )
    (net (code "89") (name "unconnected-(STM32C-PA0-Pad14)") (class "Default")
      (node (ref "STM32") (pin "14") (pinfunction "PA0_14") (pintype "bidirectional"))
    )
    (net (code "90") (name "unconnected-(STM32C-PA1-Pad15)") (class "Default")
      (node (ref "STM32") (pin "15") (pinfunction "PA1_15") (pintype "bidirectional"))
    )
    (net (code "91") (name "unconnected-(STM32C-PA2-Pad16)") (class "Default")
      (node (ref "STM32") (pin "16") (pinfunction "PA2_16") (pintype "bidirectional"))
    )
    (net (code "92") (name "unconnected-(STM32C-PA3-Pad17)") (class "Default")
      (node (ref "STM32") (pin "17") (pinfunction "PA3_17") (pintype "bidirectional"))
    )
    (net (code "93") (name "unconnected-(STM32D-PB10-Pad29)") (class "Default")
      (node (ref "STM32") (pin "29") (pinfunction "PB10_29") (pintype "bidirectional"))
    )
    (net (code "94") (name "unconnected-(STM32D-PB11-Pad30)") (class "Default")
      (node (ref "STM32") (pin "30") (pinfunction "PB11_30") (pintype "bidirectional"))
    )
    (net (code "95") (name "unconnected-(STM32E-PB2-Pad28)") (class "Default")
      (node (ref "STM32") (pin "28") (pinfunction "PB2_28") (pintype "bidirectional"))
    )
    (net (code "96") (name "unconnected-(STM32F-PC9-Pad40)") (class "Default")
      (node (ref "STM32") (pin "40") (pinfunction "PC9_40") (pintype "bidirectional"))
    )
    (net (code "97") (name "unconnected-(STM32F-PC13-Pad2)") (class "Default")
      (node (ref "STM32") (pin "2") (pinfunction "PC13_2") (pintype "bidirectional"))
    )
    (net (code "98") (name "unconnected-(STM32F-PC14-Pad3)") (class "Default")
      (node (ref "STM32") (pin "3") (pinfunction "PC14_3") (pintype "bidirectional"))
    )
    (net (code "99") (name "unconnected-(STM32G-PC0-Pad8)") (class "Default")
      (node (ref "STM32") (pin "8") (pinfunction "PC0_8") (pintype "bidirectional"))
    )
    (net (code "100") (name "unconnected-(STM32G-PC4-Pad24)") (class "Default")
      (node (ref "STM32") (pin "24") (pinfunction "PC4_24") (pintype "bidirectional"))
    )
    (net (code "101") (name "unconnected-(STM32G-PC5-Pad25)") (class "Default")
      (node (ref "STM32") (pin "25") (pinfunction "PC5_25") (pintype "bidirectional"))
    )
    (net (code "102") (name "unconnected-(STM32H-PD2-Pad54)") (class "Default")
      (node (ref "STM32") (pin "54") (pinfunction "PD2_54") (pintype "bidirectional"))
    )
    (net (code "103") (name "unconnected-(VR1-ADJ-Pad4)") (class "Default")
      (node (ref "VR1") (pin "4") (pinfunction "ADJ_4") (pintype "bidirectional"))
    )
    (net (code "104") (name "unconnected-(VR1-INH-Pad5)") (class "Default")
      (node (ref "VR1") (pin "5") (pinfunction "INH_5") (pintype "bidirectional"))
    )
    (net (code "105") (name "unconnected-(VR2-BP-Pad4)") (class "Default")
      (node (ref "VR2") (pin "4") (pinfunction "BP_4") (pintype "input"))
    )
  )
)
